# 3V3_LDO.net
KiCad netlist of a schematic drawn in Altium Designer
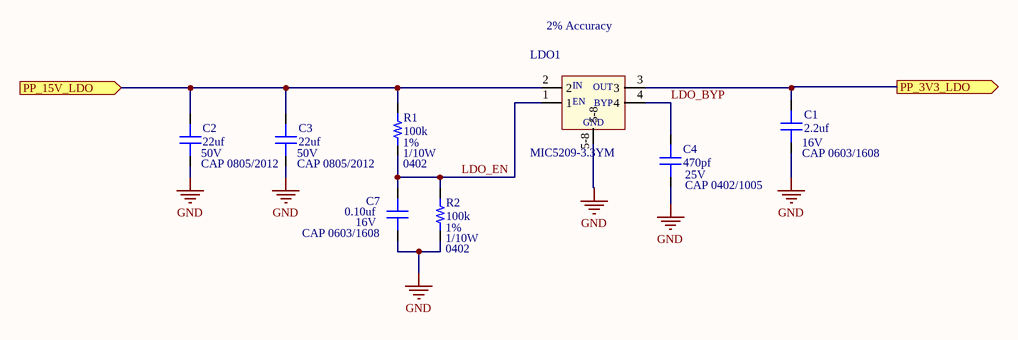
[diagram p0: 3V3_LDO.SchDoc]

(export (version "E")
  (design (tool "Eeschema 10.0.6"))
  (components
    (comp (ref "C1")
      (value "2.2uf")
      (footprint "CAP 0603/1608")
      (fields
        (field (name "VOLTAGE_RATING") "16V")
        (field (name "PACKAGE") "CAP 0603/1608")
        (field (name "Comment") "Capacitor MLCC 2.2uf 16V CAP 0603/1608")
        (field (name "CREATED_BY") "Nick Mah")
      )
      (libsource (lib "Altium-Lib") (part "Capacitor"))
    )
    (comp (ref "C2")
      (value "22uf")
      (footprint "CAP 0805/2012")
      (fields
        (field (name "VOLTAGE_RATING") "50V")
        (field (name "PACKAGE") "CAP 0805/2012")
        (field (name "Comment") "Capacitor MLCC 22uf 50V CAP 0805/2012")
        (field (name "CREATED_BY") "Nick Mah")
      )
      (libsource (lib "Altium-Lib") (part "Capacitor"))
    )
    (comp (ref "C3")
      (value "22uf")
      (footprint "CAP 0805/2012")
      (fields
        (field (name "VOLTAGE_RATING") "50V")
        (field (name "PACKAGE") "CAP 0805/2012")
        (field (name "Comment") "Capacitor MLCC 22uf 50V CAP 0805/2012")
        (field (name "CREATED_BY") "Nick Mah")
      )
      (libsource (lib "Altium-Lib") (part "Capacitor"))
    )
    (comp (ref "C4")
      (value "470pf")
      (footprint "CAP 0402/1005")
      (fields
        (field (name "VOLTAGE_RATING") "25V")
        (field (name "PACKAGE") "CAP 0402/1005")
        (field (name "Comment") "Capacitor MLCC 470pf 25V CAP 0402/1005")
        (field (name "CREATED_BY") "Nick Mah")
      )
      (libsource (lib "Altium-Lib") (part "Capacitor"))
    )
    (comp (ref "C7")
      (value "0.10uf")
      (footprint "CAP 0603/1608")
      (fields
        (field (name "VOLTAGE_RATING") "16V")
        (field (name "PACKAGE") "CAP 0603/1608")
        (field (name "Comment") "Capacitor MLCC 0.10uf 16V CAP 0603/1608")
        (field (name "CREATED_BY") "Nick Mah")
      )
      (libsource (lib "Altium-Lib") (part "Capacitor"))
    )
    (comp (ref "LDO1")
      (value "MIC5209-3.3YM")
      (footprint "SOIC-8")
      (description "IC REG LINEAR 3.3V 500MA 8SOIC")
      (fields (field (name "MFRPARTNO") "MIC5209-3.3YM-TRYM"))
      (libsource (lib "Altium-Lib") (part "MIC5209-3.3YM"))
    )
    (comp (ref "R1")
      (value "100k")
      (footprint "RES 0402/1005")
      (fields
        (field (name "TOLERANCE") "1%")
        (field (name "POWER") "1/10W")
        (field (name "PACKAGE") "0402")
        (field (name "Comment") "Resistor 100k 0402 1/10W 1%")
        (field (name "CREATED_BY") "Nick Mah")
      )
      (libsource (lib "Altium-Lib") (part "Resistor"))
    )
    (comp (ref "R2")
      (value "100k")
      (footprint "RES 0402/1005")
      (fields
        (field (name "TOLERANCE") "1%")
        (field (name "POWER") "1/10W")
        (field (name "PACKAGE") "0402")
        (field (name "Comment") "Resistor 100k 0402 1/10W 1%")
        (field (name "CREATED_BY") "Nick Mah")
      )
      (libsource (lib "Altium-Lib") (part "Resistor"))
    )
  )
  (nets
    (net (code "1") (name "/LDO_BYP") (class "Default")
      (node (ref "C4") (pin "2") (pinfunction "2_2") (pintype "passive"))
      (node (ref "LDO1") (pin "4") (pinfunction "4_4") (pintype "passive"))
    )
    (net (code "2") (name "/LDO_EN") (class "Default")
      (node (ref "C7") (pin "2") (pinfunction "2_2") (pintype "passive"))
      (node (ref "LDO1") (pin "1") (pinfunction "1_1") (pintype "passive"))
      (node (ref "R1") (pin "1") (pinfunction "1_1") (pintype "passive"))
      (node (ref "R2") (pin "2") (pinfunction "2_2") (pintype "passive"))
    )
    (net (code "3") (name "/PP_3V3_LDO") (class "Default")
      (node (ref "C1") (pin "2") (pinfunction "2_2") (pintype "passive"))
      (node (ref "LDO1") (pin "3") (pinfunction "3_3") (pintype "passive"))
    )
    (net (code "4") (name "/PP_15V_LDO") (class "Default")
      (node (ref "C2") (pin "2") (pinfunction "2_2") (pintype "passive"))
      (node (ref "C3") (pin "2") (pinfunction "2_2") (pintype "passive"))
      (node (ref "LDO1") (pin "2") (pinfunction "2_2") (pintype "passive"))
      (node (ref "R1") (pin "2") (pinfunction "2_2") (pintype "passive"))
    )
    (net (code "5") (name "GND") (class "Default")
      (node (ref "C1") (pin "1") (pinfunction "1_1") (pintype "passive"))
      (node (ref "C2") (pin "1") (pinfunction "1_1") (pintype "passive"))
      (node (ref "C3") (pin "1") (pinfunction "1_1") (pintype "passive"))
      (node (ref "C4") (pin "1") (pinfunction "1_1") (pintype "passive"))
      (node (ref "C7") (pin "1") (pinfunction "1_1") (pintype "passive"))
      (node (ref "LDO1") (pin "5-8") (pinfunction "5-8_5-8") (pintype "passive"))
      (node (ref "R2") (pin "1") (pinfunction "1_1") (pintype "passive"))
    )
  )
)
